# design.net
KiCad netlist of a schematic drawn in Altium Designer
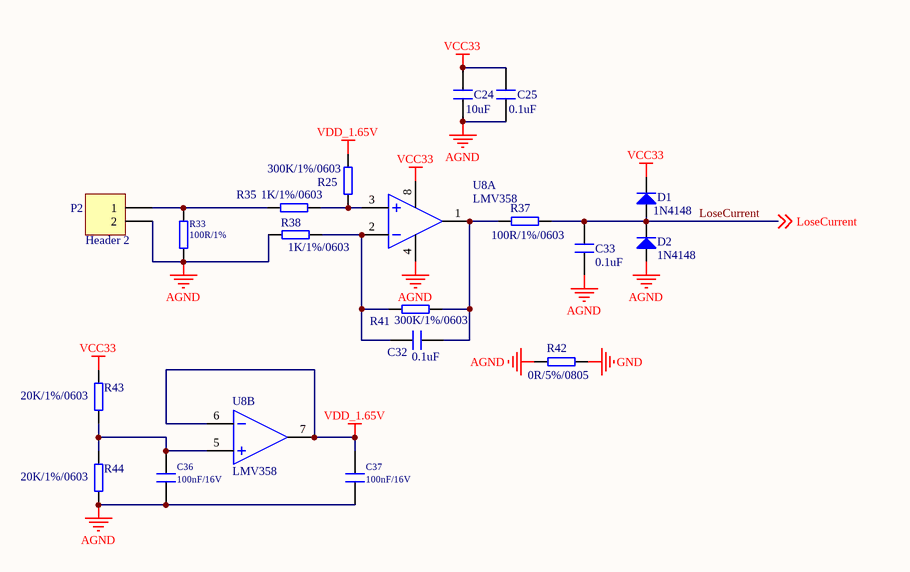
[diagram p0: 漏电流检测.SchDoc]

(export (version "E")
  (design (tool "Eeschema 10.0.6"))
  (components
    (comp (ref "C24") (value "10uF") (footprint "0603R") (libsource (lib "ES_Schematic") (part "CAP")))
    (comp (ref "C25") (value "0.1uF") (footprint "0603R") (libsource (lib "ES_Schematic") (part "CAP")))
    (comp (ref "C32") (value "0.1uF") (footprint "0603R") (libsource (lib "ES_Schematic") (part "CAP")))
    (comp (ref "C33") (value "0.1uF") (footprint "0603R") (libsource (lib "ES_Schematic") (part "CAP")))
    (comp (ref "C36") (value "100nF/16V") (footprint "0603R") (libsource (lib "ES_Schematic") (part "CAP")))
    (comp (ref "C37") (value "100nF/16V") (footprint "0603R") (libsource (lib "ES_Schematic") (part "CAP")))
    (comp (ref "D1") (value "1N4148") (footprint "1206D") (libsource (lib "ES_Schematic") (part "DIODE")))
    (comp (ref "D2") (value "1N4148") (footprint "1206D") (libsource (lib "ES_Schematic") (part "DIODE")))
    (comp (ref "P2")
      (value "Header 2")
      (footprint "CONN-TH_P5.08_KF127-5.08-2P")
      (description "Header, 2-Pin")
      (fields (field (name "PUBLISHER") "Altium Limited"))
      (libsource (lib "Miscellaneous Connectors") (part "Header 2"))
    )
    (comp (ref "R25")
      (value "300K/1%/0603")
      (footprint "0603r")
      (libsource (lib "ES_Schematic") (part "RES"))
    )
    (comp (ref "R33") (value "100R/1%") (footprint "0805R") (libsource (lib "ES_Schematic") (part "RES")))
    (comp (ref "R35") (value "1K/1%/0603") (footprint "0603r") (libsource (lib "ES_Schematic") (part "RES")))
    (comp (ref "R37")
      (value "100R/1%/0603")
      (footprint "0603r")
      (libsource (lib "ES_Schematic") (part "RES"))
    )
    (comp (ref "R38") (value "1K/1%/0603") (footprint "0603r") (libsource (lib "ES_Schematic") (part "RES")))
    (comp (ref "R41")
      (value "300K/1%/0603")
      (footprint "0603r")
      (libsource (lib "ES_Schematic") (part "RES"))
    )
    (comp (ref "R42") (value "0R/5%/0805") (footprint "0805R") (libsource (lib "ES_Schematic") (part "RES")))
    (comp (ref "R43") (value "20K/1%/0603") (footprint "0603r") (libsource (lib "ES_Schematic") (part "RES")))
    (comp (ref "R44") (value "20K/1%/0603") (footprint "0603r") (libsource (lib "ES_Schematic") (part "RES")))
    (comp (ref "U8") (value "LMV358") (footprint "SO8") (libsource (lib "sangjian") (part "LM358")))
  )
  (nets
    (net (code "1") (name "AGND") (class "Default")
      (node (ref "C24") (pin "1") (pinfunction "1_1") (pintype "passive"))
      (node (ref "C25") (pin "1") (pinfunction "1_1") (pintype "passive"))
      (node (ref "C33") (pin "2") (pinfunction "2_2") (pintype "passive"))
      (node (ref "C36") (pin "2") (pinfunction "2_2") (pintype "passive"))
      (node (ref "C37") (pin "2") (pinfunction "2_2") (pintype "passive"))
      (node (ref "D2") (pin "2") (pinfunction "A_2") (pintype "passive"))
      (node (ref "P2") (pin "2") (pinfunction "2_2") (pintype "passive"))
      (node (ref "R33") (pin "1") (pinfunction "1_1") (pintype "passive"))
      (node (ref "R38") (pin "2") (pinfunction "2_2") (pintype "passive"))
      (node (ref "R42") (pin "2") (pinfunction "2_2") (pintype "passive"))
      (node (ref "R44") (pin "2") (pinfunction "2_2") (pintype "passive"))
      (node (ref "U8") (pin "4") (pinfunction "4_4") (pintype "passive"))
    )
    (net (code "2") (name "GND") (class "Default")
      (node (ref "R42") (pin "1") (pinfunction "1_1") (pintype "passive"))
    )
    (net (code "3") (name "LoseCurrent") (class "Default")
      (node (ref "C33") (pin "1") (pinfunction "1_1") (pintype "passive"))
      (node (ref "D1") (pin "2") (pinfunction "A_2") (pintype "passive"))
      (node (ref "D2") (pin "1") (pinfunction "K_1") (pintype "passive"))
      (node (ref "R37") (pin "1") (pinfunction "1_1") (pintype "passive"))
    )
    (net (code "4") (name "Net-(C32-Pad1)") (class "Default")
      (node (ref "C32") (pin "1") (pinfunction "1_1") (pintype "passive"))
      (node (ref "R38") (pin "1") (pinfunction "1_1") (pintype "passive"))
      (node (ref "R41") (pin "2") (pinfunction "2_2") (pintype "passive"))
      (node (ref "U8") (pin "2") (pinfunction "2_2") (pintype "passive"))
    )
    (net (code "5") (name "Net-(C32-Pad2)") (class "Default")
      (node (ref "C32") (pin "2") (pinfunction "2_2") (pintype "passive"))
      (node (ref "R37") (pin "2") (pinfunction "2_2") (pintype "passive"))
      (node (ref "R41") (pin "1") (pinfunction "1_1") (pintype "passive"))
      (node (ref "U8") (pin "1") (pinfunction "1_1") (pintype "passive"))
    )
    (net (code "6") (name "Net-(C36-Pad1)") (class "Default")
      (node (ref "C36") (pin "1") (pinfunction "1_1") (pintype "passive"))
      (node (ref "R43") (pin "2") (pinfunction "2_2") (pintype "passive"))
      (node (ref "R44") (pin "1") (pinfunction "1_1") (pintype "passive"))
      (node (ref "U8") (pin "5") (pinfunction "5_5") (pintype "passive"))
    )
    (net (code "7") (name "Net-(P2-Pad1)") (class "Default")
      (node (ref "P2") (pin "1") (pinfunction "1_1") (pintype "passive"))
      (node (ref "R33") (pin "2") (pinfunction "2_2") (pintype "passive"))
      (node (ref "R35") (pin "2") (pinfunction "2_2") (pintype "passive"))
    )
    (net (code "8") (name "Net-(R25-Pad2)") (class "Default")
      (node (ref "R25") (pin "2") (pinfunction "2_2") (pintype "passive"))
      (node (ref "R35") (pin "1") (pinfunction "1_1") (pintype "passive"))
      (node (ref "U8") (pin "3") (pinfunction "3_3") (pintype "passive"))
    )
    (net (code "9") (name "VCC33") (class "Default")
      (node (ref "C24") (pin "2") (pinfunction "2_2") (pintype "passive"))
      (node (ref "C25") (pin "2") (pinfunction "2_2") (pintype "passive"))
      (node (ref "D1") (pin "1") (pinfunction "K_1") (pintype "passive"))
      (node (ref "R43") (pin "1") (pinfunction "1_1") (pintype "passive"))
      (node (ref "U8") (pin "8") (pinfunction "8_8") (pintype "passive"))
    )
    (net (code "10") (name "VDD_1.65V") (class "Default")
      (node (ref "C37") (pin "1") (pinfunction "1_1") (pintype "passive"))
      (node (ref "R25") (pin "1") (pinfunction "1_1") (pintype "passive"))
      (node (ref "U8") (pin "6") (pinfunction "6_6") (pintype "passive"))
      (node (ref "U8") (pin "7") (pinfunction "7_7") (pintype "passive"))
    )
  )
)
